# Demo_Board.net
KiCad netlist of a schematic drawn in EAGLE
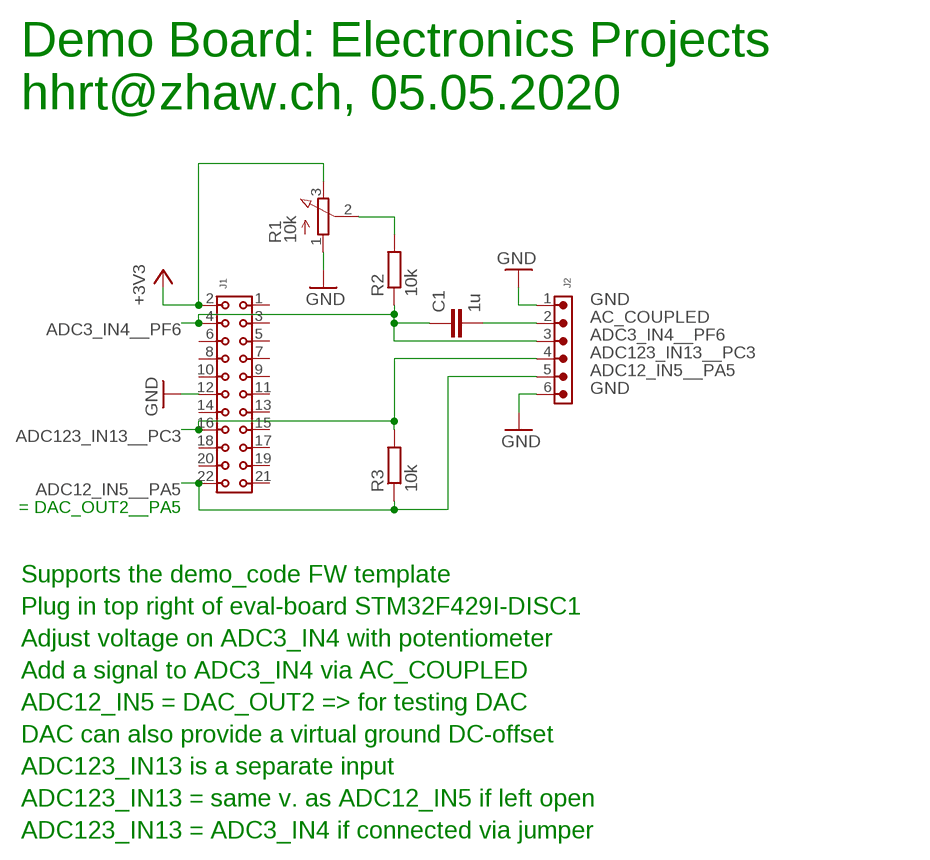
[diagram p0: schematic, sheet 1]

(export (version "E")
  (design (tool "Eeschema 10.0.6"))
  (components
    (comp (ref "C1")
      (value "1u")
      (footprint "eagle-import:C0805")
      (libsource (lib "eagle-import") (part "C-EUC0805"))
    )
    (comp (ref "J1")
      (value "6130XX21821_61302221821")
      (footprint "eagle-import:61302221821")
      (libsource (lib "eagle-import") (part "6130XX21821_61302221821"))
    )
    (comp (ref "J2")
      (value "6130XX11121_61300611121")
      (footprint "eagle-import:61300611121")
      (libsource (lib "eagle-import") (part "6130XX11121_61300611121"))
    )
    (comp (ref "R1")
      (value "10k")
      (footprint "eagle-import:EVUF")
      (libsource (lib "eagle-import") (part "EVUAF2"))
    )
    (comp (ref "R2")
      (value "10k")
      (footprint "eagle-import:R0805")
      (libsource (lib "eagle-import") (part "R-EU_R0805"))
    )
    (comp (ref "R3")
      (value "10k")
      (footprint "eagle-import:R0805")
      (libsource (lib "eagle-import") (part "R-EU_R0805"))
    )
  )
  (nets
    (net (code "1") (name "+3V3") (class "Default")
      (node (ref "J1") (pin "2") (pinfunction "2_2") (pintype "passive"))
      (node (ref "R1") (pin "3") (pinfunction "E_3") (pintype "passive"))
    )
    (net (code "2") (name "/AC_COUPLED") (class "Default")
      (node (ref "C1") (pin "2") (pinfunction "2_2") (pintype "passive"))
      (node (ref "J2") (pin "2") (pinfunction "2_2") (pintype "passive"))
    )
    (net (code "3") (name "/ADC3_IN4__PF6") (class "Default")
      (node (ref "C1") (pin "1") (pinfunction "1_1") (pintype "passive"))
      (node (ref "J1") (pin "4") (pinfunction "4_4") (pintype "passive"))
      (node (ref "J2") (pin "3") (pinfunction "3_3") (pintype "passive"))
      (node (ref "R2") (pin "1") (pinfunction "1_1") (pintype "passive"))
    )
    (net (code "4") (name "/ADC12_IN5__PA5") (class "Default")
      (node (ref "J1") (pin "22") (pinfunction "22_22") (pintype "passive"))
      (node (ref "J2") (pin "5") (pinfunction "5_5") (pintype "passive"))
      (node (ref "R3") (pin "1") (pinfunction "1_1") (pintype "passive"))
    )
    (net (code "5") (name "/ADC123_IN13__PC3") (class "Default")
      (node (ref "J1") (pin "16") (pinfunction "16_16") (pintype "passive"))
      (node (ref "J2") (pin "4") (pinfunction "4_4") (pintype "passive"))
      (node (ref "R3") (pin "2") (pinfunction "2_2") (pintype "passive"))
    )
    (net (code "6") (name "GND") (class "Default")
      (node (ref "J1") (pin "12") (pinfunction "12_12") (pintype "passive"))
      (node (ref "J2") (pin "1") (pinfunction "1_1") (pintype "passive"))
      (node (ref "J2") (pin "6") (pinfunction "6_6") (pintype "passive"))
      (node (ref "R1") (pin "1") (pinfunction "A_1") (pintype "passive"))
    )
    (net (code "7") (name "Net-(R1-S)") (class "Default")
      (node (ref "R1") (pin "2") (pinfunction "S_2") (pintype "passive"))
      (node (ref "R2") (pin "2") (pinfunction "2_2") (pintype "passive"))
    )
    (net (code "8") (name "unconnected-(J1-Pad1)") (class "Default")
      (node (ref "J1") (pin "1") (pinfunction "1_1") (pintype "passive"))
    )
    (net (code "9") (name "unconnected-(J1-Pad3)") (class "Default")
      (node (ref "J1") (pin "3") (pinfunction "3_3") (pintype "passive"))
    )
    (net (code "10") (name "unconnected-(J1-Pad5)") (class "Default")
      (node (ref "J1") (pin "5") (pinfunction "5_5") (pintype "passive"))
    )
    (net (code "11") (name "unconnected-(J1-Pad6)") (class "Default")
      (node (ref "J1") (pin "6") (pinfunction "6_6") (pintype "passive"))
    )
    (net (code "12") (name "unconnected-(J1-Pad7)") (class "Default")
      (node (ref "J1") (pin "7") (pinfunction "7_7") (pintype "passive"))
    )
    (net (code "13") (name "unconnected-(J1-Pad8)") (class "Default")
      (node (ref "J1") (pin "8") (pinfunction "8_8") (pintype "passive"))
    )
    (net (code "14") (name "unconnected-(J1-Pad9)") (class "Default")
      (node (ref "J1") (pin "9") (pinfunction "9_9") (pintype "passive"))
    )
    (net (code "15") (name "unconnected-(J1-Pad10)") (class "Default")
      (node (ref "J1") (pin "10") (pinfunction "10_10") (pintype "passive"))
    )
    (net (code "16") (name "unconnected-(J1-Pad11)") (class "Default")
      (node (ref "J1") (pin "11") (pinfunction "11_11") (pintype "passive"))
    )
    (net (code "17") (name "unconnected-(J1-Pad13)") (class "Default")
      (node (ref "J1") (pin "13") (pinfunction "13_13") (pintype "passive"))
    )
    (net (code "18") (name "unconnected-(J1-Pad14)") (class "Default")
      (node (ref "J1") (pin "14") (pinfunction "14_14") (pintype "passive"))
    )
    (net (code "19") (name "unconnected-(J1-Pad15)") (class "Default")
      (node (ref "J1") (pin "15") (pinfunction "15_15") (pintype "passive"))
    )
    (net (code "20") (name "unconnected-(J1-Pad17)") (class "Default")
      (node (ref "J1") (pin "17") (pinfunction "17_17") (pintype "passive"))
    )
    (net (code "21") (name "unconnected-(J1-Pad18)") (class "Default")
      (node (ref "J1") (pin "18") (pinfunction "18_18") (pintype "passive"))
    )
    (net (code "22") (name "unconnected-(J1-Pad19)") (class "Default")
      (node (ref "J1") (pin "19") (pinfunction "19_19") (pintype "passive"))
    )
    (net (code "23") (name "unconnected-(J1-Pad20)") (class "Default")
      (node (ref "J1") (pin "20") (pinfunction "20_20") (pintype "passive"))
    )
    (net (code "24") (name "unconnected-(J1-Pad21)") (class "Default")
      (node (ref "J1") (pin "21") (pinfunction "21_21") (pintype "passive"))
    )
  )
)
